# main_board.net
KiCad netlist of a schematic drawn in EAGLE
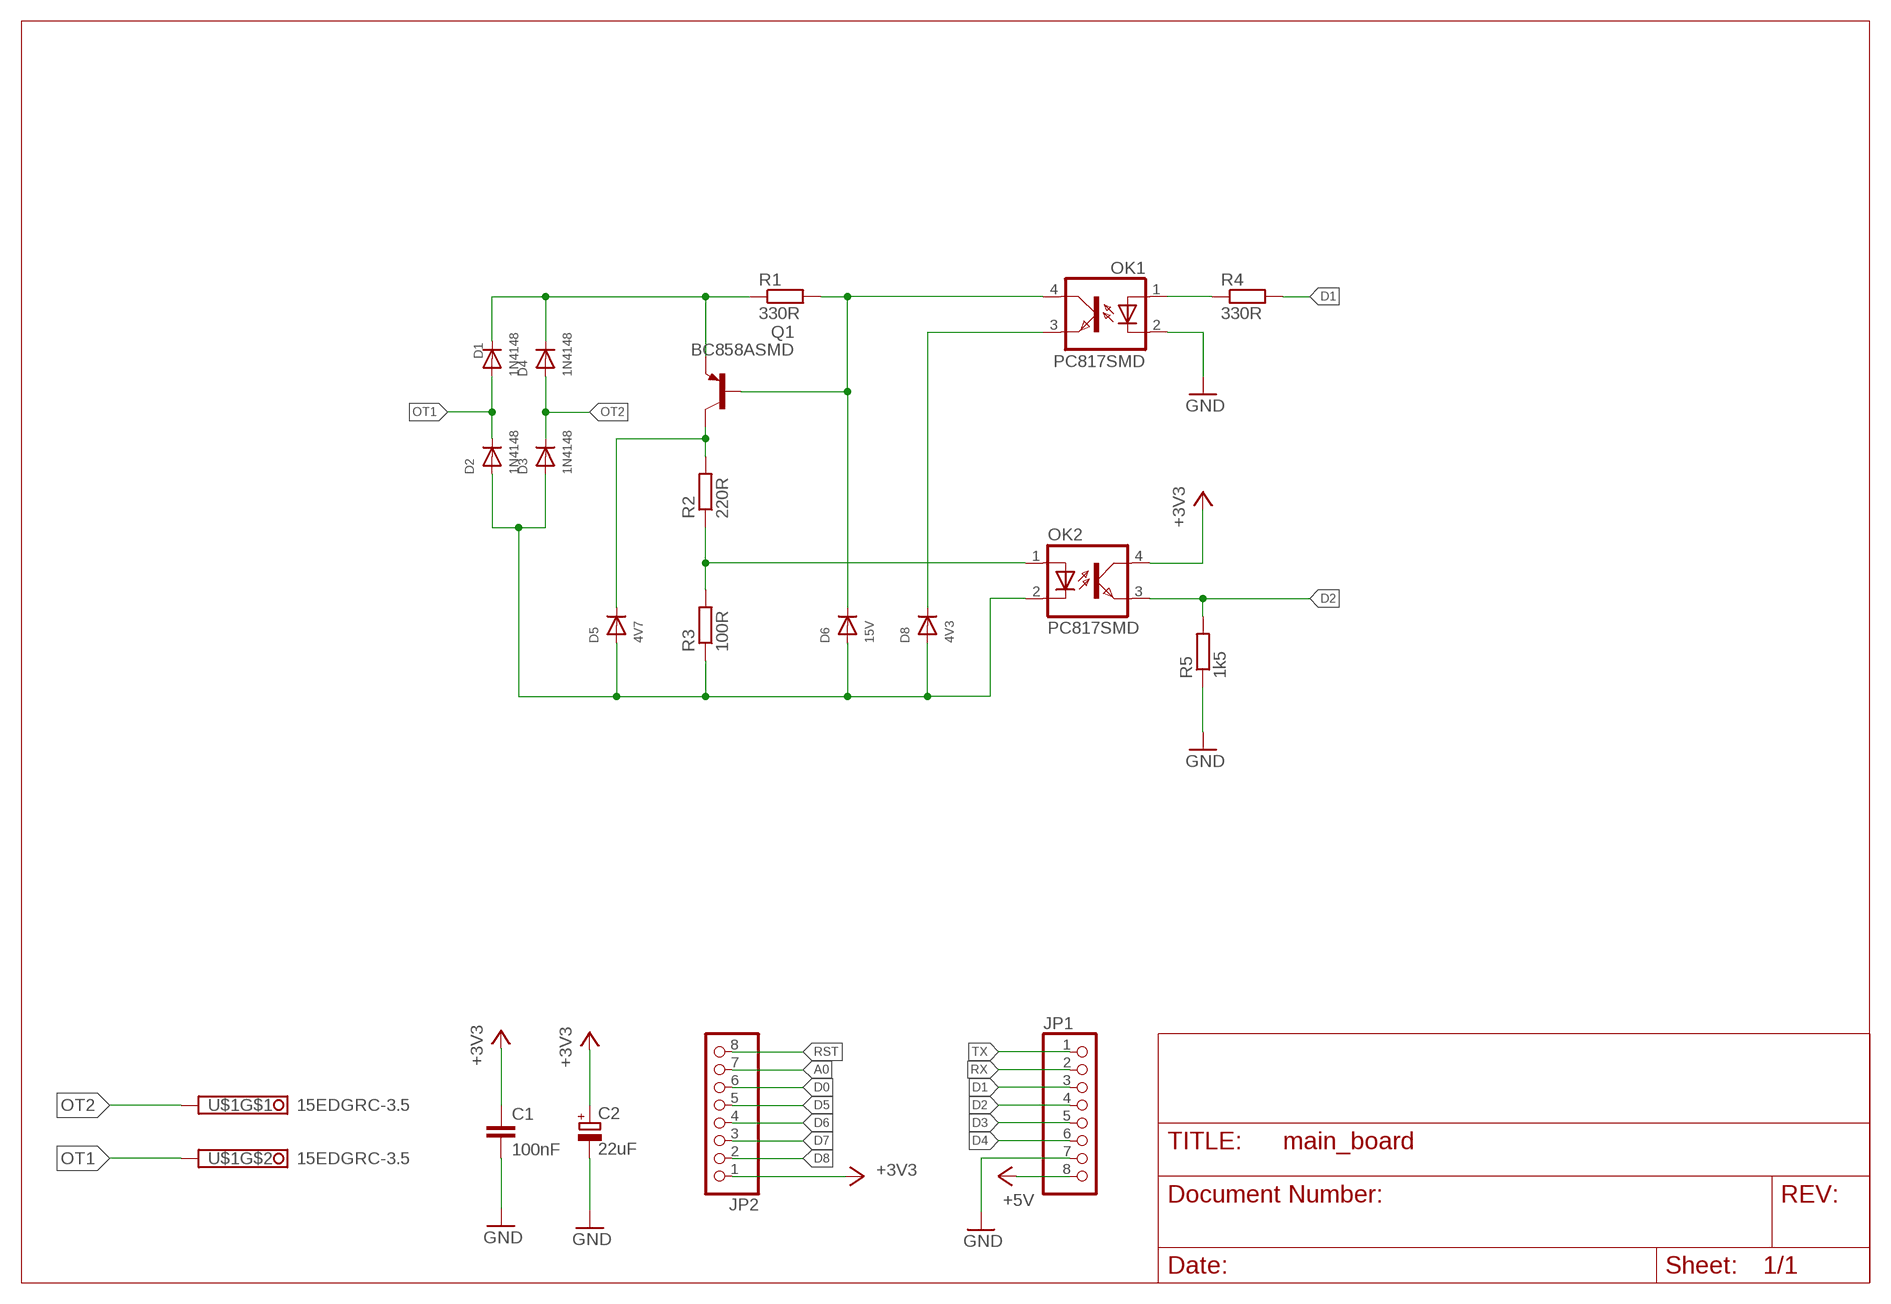
[diagram p0: schematic, sheet 1]

(export (version "E")
  (design (tool "Eeschema 10.0.6"))
  (components
    (comp (ref "C1")
      (value "100nF")
      (footprint "eagle-import:C0805")
      (libsource (lib "eagle-import") (part "C-EUC0805"))
    )
    (comp (ref "C2")
      (value "22uF")
      (footprint "eagle-import:C_6032-28R")
      (libsource (lib "eagle-import") (part "CPOL-EUC/6032-28R"))
    )
    (comp (ref "D1")
      (value "1N4148")
      (footprint "eagle-import:SOD-123")
      (libsource (lib "eagle-import") (part "DIODESOD-123"))
    )
    (comp (ref "D2")
      (value "1N4148")
      (footprint "eagle-import:SOD-123")
      (libsource (lib "eagle-import") (part "DIODESOD-123"))
    )
    (comp (ref "D3")
      (value "1N4148")
      (footprint "eagle-import:SOD-123")
      (libsource (lib "eagle-import") (part "DIODESOD-123"))
    )
    (comp (ref "D4")
      (value "1N4148")
      (footprint "eagle-import:SOD-123")
      (libsource (lib "eagle-import") (part "DIODESOD-123"))
    )
    (comp (ref "D5")
      (value "4V7")
      (footprint "eagle-import:SMADIODE")
      (libsource (lib "eagle-import") (part "DIODESMA"))
    )
    (comp (ref "D6")
      (value "15V")
      (footprint "eagle-import:SMADIODE")
      (libsource (lib "eagle-import") (part "DIODESMA"))
    )
    (comp (ref "D8")
      (value "4V3")
      (footprint "eagle-import:SMADIODE")
      (libsource (lib "eagle-import") (part "DIODESMA"))
    )
    (comp (ref "JP1")
      (value "PINHD-1X8")
      (footprint "eagle-import:1X08")
      (libsource (lib "eagle-import") (part "PINHD-1X8"))
    )
    (comp (ref "JP2")
      (value "PINHD-1X8")
      (footprint "eagle-import:1X08")
      (libsource (lib "eagle-import") (part "PINHD-1X8"))
    )
    (comp (ref "OK1")
      (value "PC817SMD")
      (footprint "eagle-import:DIL4-SMD")
      (libsource (lib "eagle-import") (part "PC817SMD"))
    )
    (comp (ref "OK2")
      (value "PC817SMD")
      (footprint "eagle-import:DIL4-SMD")
      (libsource (lib "eagle-import") (part "PC817SMD"))
    )
    (comp (ref "Q1")
      (value "BC858ASMD")
      (footprint "eagle-import:SOT23-BEC")
      (libsource (lib "eagle-import") (part "BC858SMDA"))
    )
    (comp (ref "R1")
      (value "330R")
      (footprint "eagle-import:M0805")
      (libsource (lib "eagle-import") (part "R-EU_M0805"))
    )
    (comp (ref "R2")
      (value "220R")
      (footprint "eagle-import:M0805")
      (libsource (lib "eagle-import") (part "R-EU_M0805"))
    )
    (comp (ref "R3")
      (value "100R")
      (footprint "eagle-import:M0805")
      (libsource (lib "eagle-import") (part "R-EU_M0805"))
    )
    (comp (ref "R4")
      (value "330R")
      (footprint "eagle-import:M0805")
      (libsource (lib "eagle-import") (part "R-EU_M0805"))
    )
    (comp (ref "R5")
      (value "1k5")
      (footprint "eagle-import:M0805")
      (libsource (lib "eagle-import") (part "R-EU_M0805"))
    )
    (comp (ref "U$1")
      (value "15EDGRC-3.5")
      (footprint "eagle-import:15EDGRC-3.5_2P")
      (libsource (lib "eagle-import") (part "15EDGRC-3.5"))
    )
  )
  (nets
    (net (code "1") (name "+3V3") (class "Default")
      (node (ref "C1") (pin "1") (pinfunction "1_1") (pintype "passive"))
      (node (ref "C2") (pin "+") (pinfunction "+_+") (pintype "passive"))
      (node (ref "JP2") (pin "1") (pinfunction "1_1") (pintype "passive"))
      (node (ref "OK2") (pin "4") (pinfunction "COL_4") (pintype "passive"))
    )
    (net (code "2") (name "+5V") (class "Default")
      (node (ref "JP1") (pin "8") (pinfunction "8_8") (pintype "passive"))
    )
    (net (code "3") (name "A0") (class "Default")
      (node (ref "JP2") (pin "7") (pinfunction "7_7") (pintype "passive"))
    )
    (net (code "4") (name "D0") (class "Default")
      (node (ref "JP2") (pin "6") (pinfunction "6_6") (pintype "passive"))
    )
    (net (code "5") (name "D1") (class "Default")
      (node (ref "JP1") (pin "3") (pinfunction "3_3") (pintype "passive"))
      (node (ref "R4") (pin "2") (pinfunction "2_2") (pintype "passive"))
    )
    (net (code "6") (name "D2") (class "Default")
      (node (ref "JP1") (pin "4") (pinfunction "4_4") (pintype "passive"))
      (node (ref "OK2") (pin "3") (pinfunction "EMIT_3") (pintype "passive"))
      (node (ref "R5") (pin "2") (pinfunction "2_2") (pintype "passive"))
    )
    (net (code "7") (name "D3") (class "Default")
      (node (ref "JP1") (pin "5") (pinfunction "5_5") (pintype "passive"))
    )
    (net (code "8") (name "D4") (class "Default")
      (node (ref "JP1") (pin "6") (pinfunction "6_6") (pintype "passive"))
    )
    (net (code "9") (name "D5") (class "Default")
      (node (ref "JP2") (pin "5") (pinfunction "5_5") (pintype "passive"))
    )
    (net (code "10") (name "D6") (class "Default")
      (node (ref "JP2") (pin "4") (pinfunction "4_4") (pintype "passive"))
    )
    (net (code "11") (name "D7") (class "Default")
      (node (ref "JP2") (pin "3") (pinfunction "3_3") (pintype "passive"))
    )
    (net (code "12") (name "D8") (class "Default")
      (node (ref "JP2") (pin "2") (pinfunction "2_2") (pintype "passive"))
    )
    (net (code "13") (name "GND") (class "Default")
      (node (ref "C1") (pin "2") (pinfunction "2_2") (pintype "passive"))
      (node (ref "C2") (pin "-") (pinfunction "-_-") (pintype "passive"))
      (node (ref "JP1") (pin "7") (pinfunction "7_7") (pintype "passive"))
      (node (ref "OK1") (pin "2") (pinfunction "C_2") (pintype "passive"))
      (node (ref "R5") (pin "1") (pinfunction "1_1") (pintype "passive"))
    )
    (net (code "14") (name "Net-(D1-PadC)") (class "Default")
      (node (ref "D1") (pin "C") (pinfunction "C_C") (pintype "passive"))
      (node (ref "D4") (pin "C") (pinfunction "C_C") (pintype "passive"))
      (node (ref "Q1") (pin "E") (pinfunction "E_E") (pintype "passive"))
      (node (ref "R1") (pin "1") (pinfunction "1_1") (pintype "passive"))
    )
    (net (code "15") (name "Net-(D5-PadC)") (class "Default")
      (node (ref "D5") (pin "C") (pinfunction "C_C") (pintype "passive"))
      (node (ref "Q1") (pin "C") (pinfunction "C_C") (pintype "passive"))
      (node (ref "R2") (pin "2") (pinfunction "2_2") (pintype "passive"))
    )
    (net (code "16") (name "Net-(OK1-A)") (class "Default")
      (node (ref "OK1") (pin "1") (pinfunction "A_1") (pintype "passive"))
      (node (ref "R4") (pin "1") (pinfunction "1_1") (pintype "passive"))
    )
    (net (code "17") (name "Net-(OK1-COL)") (class "Default")
      (node (ref "D6") (pin "C") (pinfunction "C_C") (pintype "passive"))
      (node (ref "OK1") (pin "4") (pinfunction "COL_4") (pintype "passive"))
      (node (ref "Q1") (pin "B") (pinfunction "B_B") (pintype "passive"))
      (node (ref "R1") (pin "2") (pinfunction "2_2") (pintype "passive"))
    )
    (net (code "18") (name "Net-(OK1-EMIT)") (class "Default")
      (node (ref "D8") (pin "C") (pinfunction "C_C") (pintype "passive"))
      (node (ref "OK1") (pin "3") (pinfunction "EMIT_3") (pintype "passive"))
    )
    (net (code "19") (name "Net-(OK2-A)") (class "Default")
      (node (ref "OK2") (pin "1") (pinfunction "A_1") (pintype "passive"))
      (node (ref "R2") (pin "1") (pinfunction "1_1") (pintype "passive"))
      (node (ref "R3") (pin "2") (pinfunction "2_2") (pintype "passive"))
    )
    (net (code "20") (name "Net-(OK2-C)") (class "Default")
      (node (ref "D2") (pin "A") (pinfunction "A_A") (pintype "passive"))
      (node (ref "D3") (pin "A") (pinfunction "A_A") (pintype "passive"))
      (node (ref "D5") (pin "A") (pinfunction "A_A") (pintype "passive"))
      (node (ref "D6") (pin "A") (pinfunction "A_A") (pintype "passive"))
      (node (ref "D8") (pin "A") (pinfunction "A_A") (pintype "passive"))
      (node (ref "OK2") (pin "2") (pinfunction "C_2") (pintype "passive"))
      (node (ref "R3") (pin "1") (pinfunction "1_1") (pintype "passive"))
    )
    (net (code "21") (name "OT1") (class "Default")
      (node (ref "D1") (pin "A") (pinfunction "A_A") (pintype "passive"))
      (node (ref "D2") (pin "C") (pinfunction "C_C") (pintype "passive"))
      (node (ref "U$1") (pin "P$4") (pinfunction "K_P$4") (pintype "passive"))
    )
    (net (code "22") (name "OT2") (class "Default")
      (node (ref "D3") (pin "C") (pinfunction "C_C") (pintype "passive"))
      (node (ref "D4") (pin "A") (pinfunction "A_A") (pintype "passive"))
      (node (ref "U$1") (pin "P$3") (pinfunction "K_P$3") (pintype "passive"))
    )
    (net (code "23") (name "RST") (class "Default")
      (node (ref "JP2") (pin "8") (pinfunction "8_8") (pintype "passive"))
    )
    (net (code "24") (name "RX") (class "Default")
      (node (ref "JP1") (pin "2") (pinfunction "2_2") (pintype "passive"))
    )
    (net (code "25") (name "TX") (class "Default")
      (node (ref "JP1") (pin "1") (pinfunction "1_1") (pintype "passive"))
    )
  )
)
